# cameraTri-v1_1.net
KiCad netlist of a schematic drawn in Altium Designer
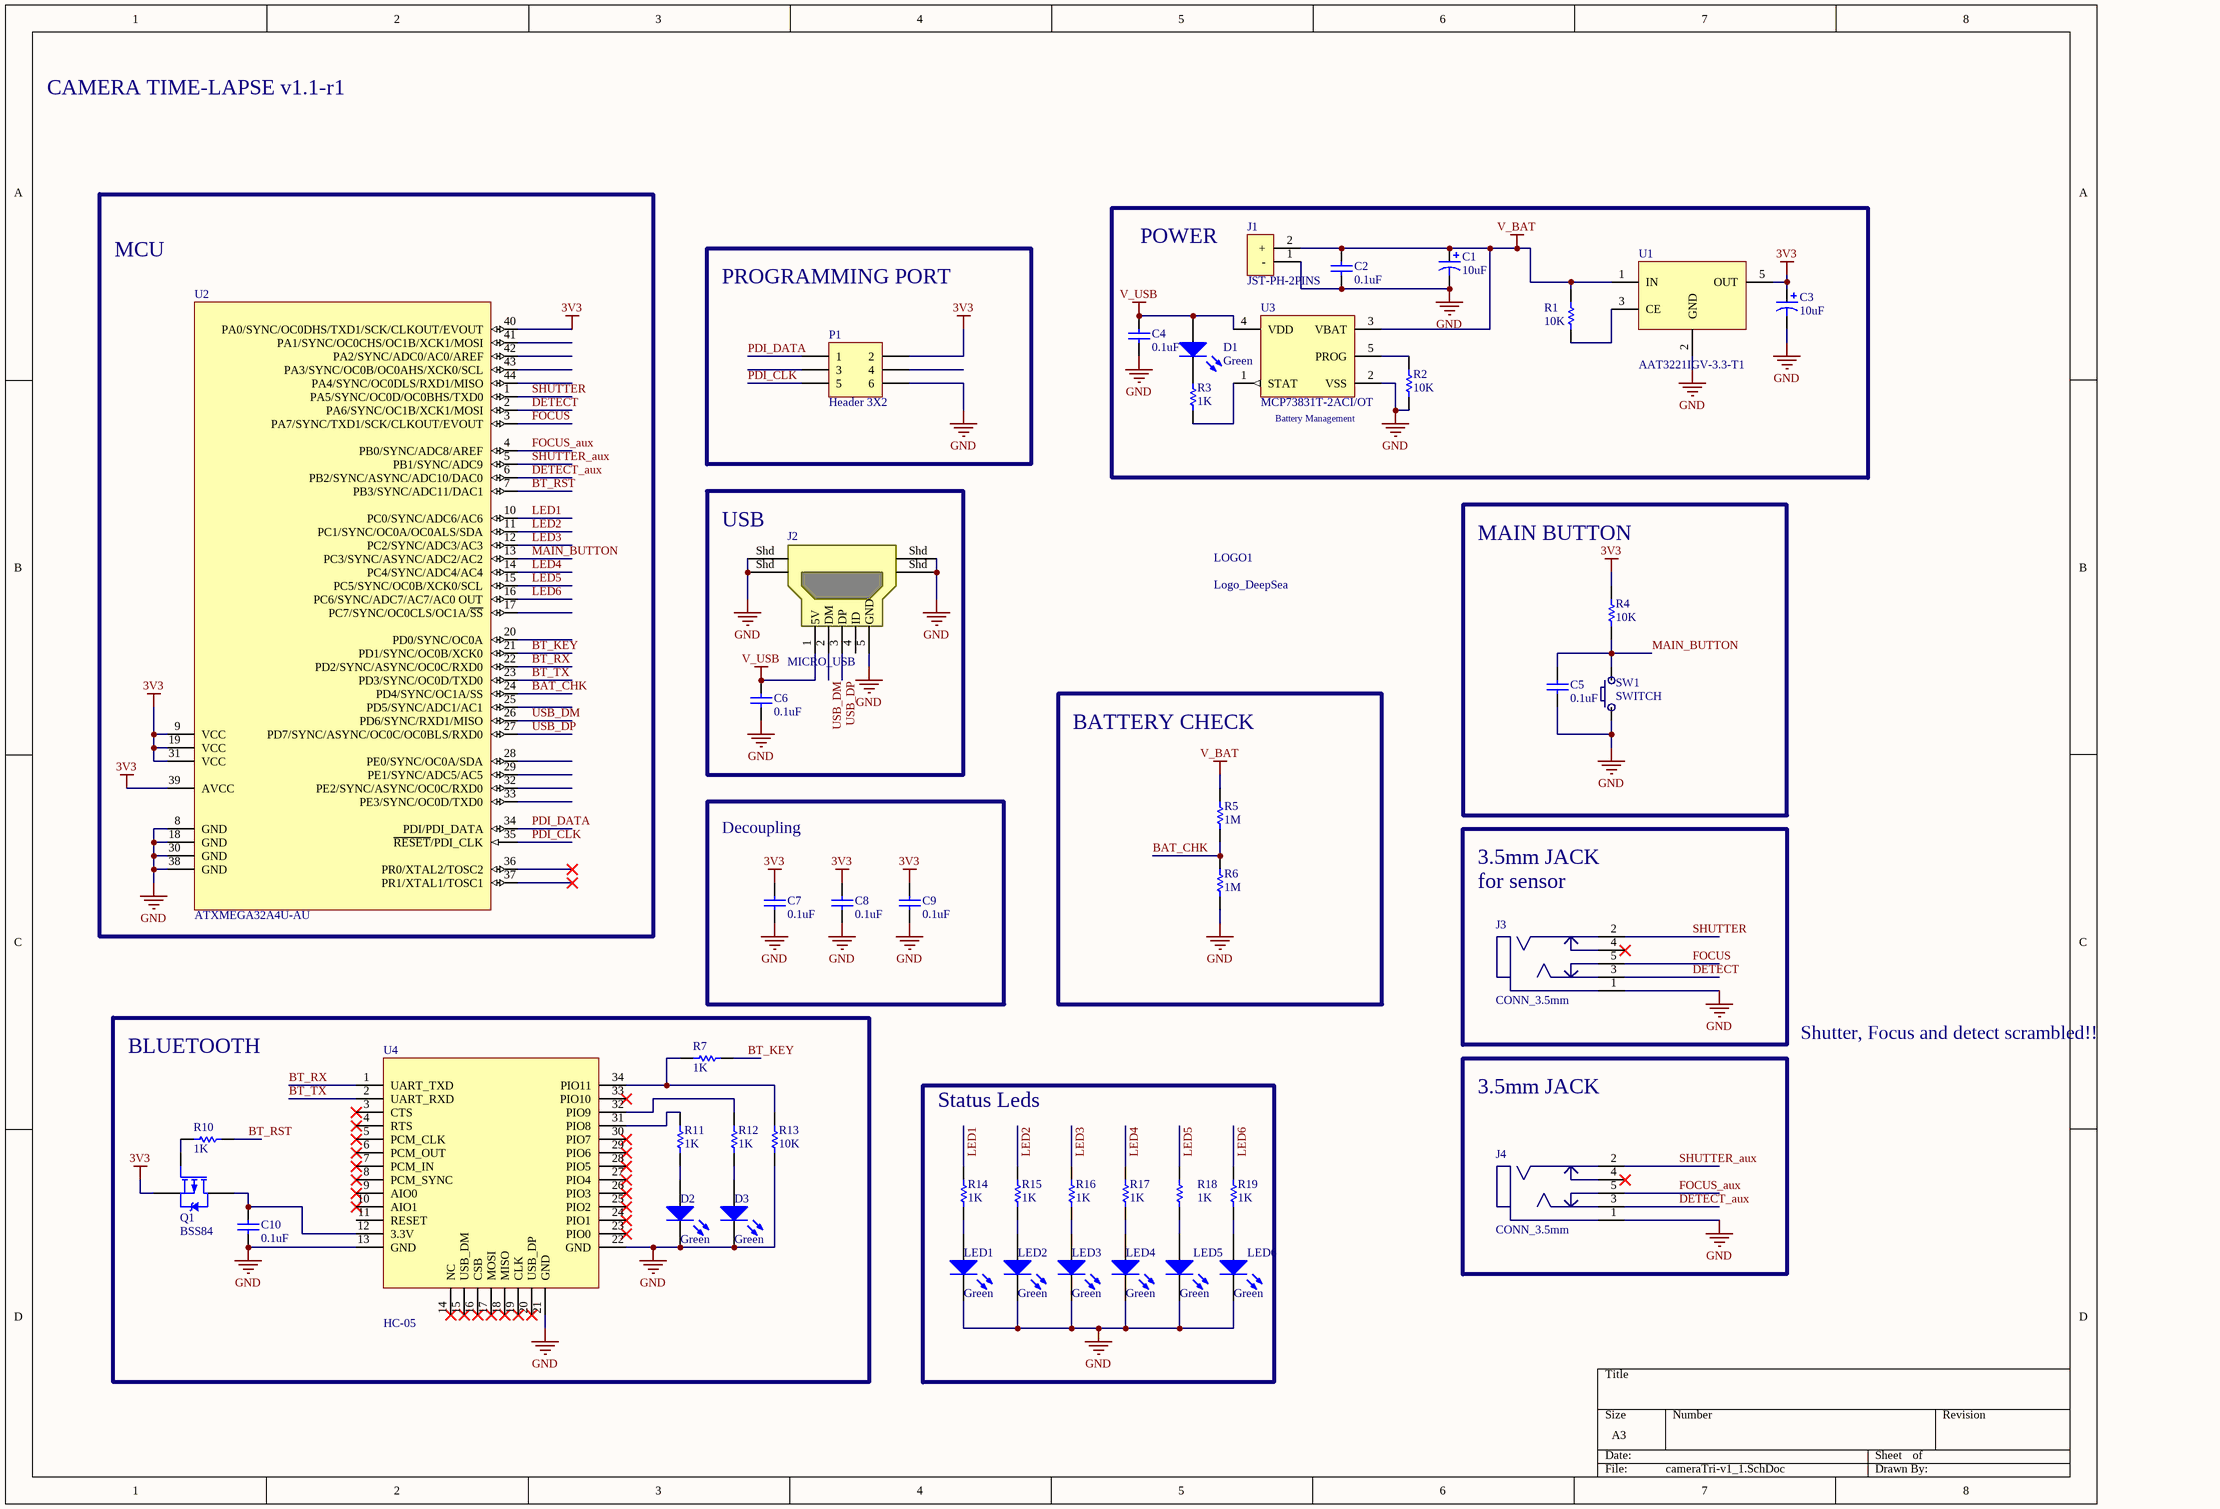
[diagram p0: cameraTri-v1_1.SchDoc]

(export (version "E")
  (design (tool "Eeschema 10.0.6"))
  (components
    (comp (ref "C1") (value "10uF") (footprint "C_TANT_A_3216_N") (libsource (lib "General") (part "CP_SMD")))
    (comp (ref "C2") (value "0.1uF") (footprint "C0603_N") (libsource (lib "General") (part "C_SMD")))
    (comp (ref "C3") (value "10uF") (footprint "C_TANT_A_3216_N") (libsource (lib "General") (part "CP_SMD")))
    (comp (ref "C4") (value "0.1uF") (footprint "C0603_N") (libsource (lib "General") (part "C_SMD")))
    (comp (ref "C5") (value "0.1uF") (footprint "C0603_N") (libsource (lib "General") (part "C_SMD")))
    (comp (ref "C6") (value "0.1uF") (footprint "C0603_N") (libsource (lib "General") (part "C_SMD")))
    (comp (ref "C7") (value "0.1uF") (footprint "C0603_N") (libsource (lib "General") (part "C_SMD")))
    (comp (ref "C8") (value "0.1uF") (footprint "C0603_N") (libsource (lib "General") (part "C_SMD")))
    (comp (ref "C9") (value "0.1uF") (footprint "C0603_N") (libsource (lib "General") (part "C_SMD")))
    (comp (ref "C10") (value "0.1uF") (footprint "C0603_N") (libsource (lib "General") (part "C_SMD")))
    (comp (ref "D1")
      (value "Green")
      (footprint "R0603_N")
      (fields (field (name "COLOR") "Green"))
      (libsource (lib "discrete") (part "LED_SMD"))
    )
    (comp (ref "D2")
      (value "Green")
      (footprint "R0603_N")
      (fields (field (name "COLOR") "Green"))
      (libsource (lib "discrete") (part "LED_SMD"))
    )
    (comp (ref "D3")
      (value "Green")
      (footprint "R0603_N")
      (fields (field (name "COLOR") "Green"))
      (libsource (lib "discrete") (part "LED_SMD"))
    )
    (comp (ref "J1")
      (value "JST-PH-2PINS")
      (footprint "JST-PH-2")
      (description "CONN HEADER PH SIDE 2POS 2MM SMD")
      (fields
        (field (name "MANUFACTURER") "JST Sales America Inc")
        (field (name "MANUFACTURER PART NUMBER") "S2B-PH-SM4-TB(LF)(SN)")
      )
      (libsource (lib "General") (part "JST-PH-2PINS"))
    )
    (comp (ref "J2")
      (value "MICRO_USB")
      (footprint "USB_MICRO_SMD")
      (description "CONN USB MICRO B RECPT SMT R/A")
      (fields (field (name "MANUFACTURER") "FCI") (field (name "MANUFACTURER PART NUMBER") "10118194-0001LF"))
      (libsource (lib "General") (part "MICRO_USB"))
    )
    (comp (ref "J3")
      (value "CONN_3.5mm")
      (footprint "JACK_3.5MM")
      (description "CONN JACK STEREO 3.5MM SMD")
      (fields
        (field (name "MANUFACTURER") "Switchcraft Inc.")
        (field (name "MANUFACTURER PART NUMBER") "35RASMT4BHNTRX")
      )
      (libsource (lib "General") (part "CONN_3.5mm"))
    )
    (comp (ref "J4")
      (value "CONN_3.5mm")
      (footprint "JACK_3.5MM")
      (description "CONN JACK STEREO 3.5MM SMD")
      (fields
        (field (name "MANUFACTURER") "Switchcraft Inc.")
        (field (name "MANUFACTURER PART NUMBER") "35RASMT4BHNTRX")
      )
      (libsource (lib "General") (part "CONN_3.5mm"))
    )
    (comp (ref "LED1")
      (value "Green")
      (footprint "R0603_N")
      (fields (field (name "COLOR") "Green"))
      (libsource (lib "discrete") (part "LED_SMD"))
    )
    (comp (ref "LED2")
      (value "Green")
      (footprint "R0603_N")
      (fields (field (name "COLOR") "Green"))
      (libsource (lib "discrete") (part "LED_SMD"))
    )
    (comp (ref "LED3")
      (value "Green")
      (footprint "R0603_N")
      (fields (field (name "COLOR") "Green"))
      (libsource (lib "discrete") (part "LED_SMD"))
    )
    (comp (ref "LED4")
      (value "Green")
      (footprint "R0603_N")
      (fields (field (name "COLOR") "Green"))
      (libsource (lib "discrete") (part "LED_SMD"))
    )
    (comp (ref "LED5")
      (value "Green")
      (footprint "R0603_N")
      (fields (field (name "COLOR") "Green"))
      (libsource (lib "discrete") (part "LED_SMD"))
    )
    (comp (ref "LED6")
      (value "Green")
      (footprint "R0603_N")
      (fields (field (name "COLOR") "Green"))
      (libsource (lib "discrete") (part "LED_SMD"))
    )
    (comp (ref "LOGO1")
      (value "Logo_DeepSea")
      (footprint "DeepSea_logo1")
      (libsource (lib "General") (part "Logo_DeepSea"))
    )
    (comp (ref "P1")
      (value "Header 3X2")
      (footprint "HDR2X3")
      (description "Header, 3-Pin, Dual row")
      (fields (field (name "PUBLISHER") "Altium Limited"))
      (libsource (lib "Miscellaneous Connectors") (part "Header 3X2"))
    )
    (comp (ref "Q1")
      (value "BSS84")
      (footprint "SOT-23_N")
      (description "MOSFET P-CH 50V 130MA SOT-23")
      (fields (field (name "MANUFACTURER") "Fairchild Semiconductor"))
      (libsource (lib "General") (part "BSS84"))
    )
    (comp (ref "R1") (value "10K") (footprint "R0603_N") (libsource (lib "discrete") (part "R_SMD")))
    (comp (ref "R2") (value "10K") (footprint "R0603_N") (libsource (lib "discrete") (part "R_SMD")))
    (comp (ref "R3") (value "1K") (footprint "R0603_N") (libsource (lib "discrete") (part "R_SMD")))
    (comp (ref "R4") (value "10K") (footprint "R0603_N") (libsource (lib "discrete") (part "R_SMD")))
    (comp (ref "R5") (value "1M") (footprint "R0603_N") (libsource (lib "discrete") (part "R_SMD")))
    (comp (ref "R6") (value "1M") (footprint "R0603_N") (libsource (lib "discrete") (part "R_SMD")))
    (comp (ref "R7") (value "1K") (footprint "R0603_N") (libsource (lib "discrete") (part "R_SMD")))
    (comp (ref "R10") (value "1K") (footprint "R0603_N") (libsource (lib "discrete") (part "R_SMD")))
    (comp (ref "R11") (value "1K") (footprint "R0603_N") (libsource (lib "discrete") (part "R_SMD")))
    (comp (ref "R12") (value "1K") (footprint "R0603_N") (libsource (lib "discrete") (part "R_SMD")))
    (comp (ref "R13") (value "10K") (footprint "R0603_N") (libsource (lib "discrete") (part "R_SMD")))
    (comp (ref "R14") (value "1K") (footprint "R0603_N") (libsource (lib "discrete") (part "R_SMD")))
    (comp (ref "R15") (value "1K") (footprint "R0603_N") (libsource (lib "discrete") (part "R_SMD")))
    (comp (ref "R16") (value "1K") (footprint "R0603_N") (libsource (lib "discrete") (part "R_SMD")))
    (comp (ref "R17") (value "1K") (footprint "R0603_N") (libsource (lib "discrete") (part "R_SMD")))
    (comp (ref "R18") (value "1K") (footprint "R0603_N") (libsource (lib "discrete") (part "R_SMD")))
    (comp (ref "R19") (value "1K") (footprint "R0603_N") (libsource (lib "discrete") (part "R_SMD")))
    (comp (ref "SW1")
      (value "SWITCH")
      (footprint "swich_foot")
      (description "SWITCH TACTILE SPST-NO 0.05A 12V")
      (fields
        (field (name "MANUFACTURER") "TE Connectivity")
        (field (name "MANUFACTURER PART NUMBER") "FSM4JSMATR")
      )
      (libsource (lib "General") (part "SWITCH"))
    )
    (comp (ref "U1")
      (value "AAT3221IGV-3.3-T1")
      (footprint "SOT-23-OT5_N")
      (description "IC REG LDO 3.3V 0.15A SOT23-5")
      (fields (field (name "MANUFACTURER") "Skyworks Solutions Inc"))
      (libsource (lib "General") (part "AAT3221IGV-3.3-T1"))
    )
    (comp (ref "U2")
      (value "ATXMEGA32A4U-AU")
      (footprint "44A_N")
      (description "IC MCU 8BIT 32KB FLASH 44TQFP")
      (fields (field (name "MANUFACTURER") "Atmel"))
      (libsource (lib "General") (part "ATXMEGA32A4U-AU"))
    )
    (comp (ref "U3")
      (value "MCP73831T-2ACI/OT")
      (footprint "SOT-23-OT5_N")
      (description "IC CONTROLLR LI-ION 4.2V SOT23-5")
      (fields (field (name "MANUFACTURER") "Microchip Technology"))
      (libsource (lib "General") (part "MCP73831T-2ACI/OT"))
    )
    (comp (ref "U4")
      (value "HC-05")
      (footprint "HC-05")
      (description "Bluetooth RS232 module")
      (libsource (lib "General") (part "HC-05"))
    )
  )
  (nets
    (net (code "1") (name "/BAT_CHK") (class "Default")
      (node (ref "R5") (pin "2") (pinfunction "2_2") (pintype "passive"))
      (node (ref "R6") (pin "1") (pinfunction "1_1") (pintype "passive"))
      (node (ref "U2") (pin "24") (pinfunction "PD4/SYNC/OC1A/SS_24") (pintype "bidirectional"))
    )
    (net (code "2") (name "/BT_KEY") (class "Default")
      (node (ref "R7") (pin "1") (pinfunction "1_1") (pintype "passive"))
      (node (ref "U2") (pin "21") (pinfunction "PD1/SYNC/OC0B/XCK0_21") (pintype "bidirectional"))
    )
    (net (code "3") (name "/BT_RST") (class "Default")
      (node (ref "R10") (pin "2") (pinfunction "2_2") (pintype "passive"))
      (node (ref "U2") (pin "7") (pinfunction "PB3/SYNC/ADC11/DAC1_7") (pintype "bidirectional"))
    )
    (net (code "4") (name "/BT_RX") (class "Default")
      (node (ref "U2") (pin "22") (pinfunction "PD2/SYNC/ASYNC/OC0C/RXD0_22") (pintype "bidirectional"))
      (node (ref "U4") (pin "1") (pinfunction "UART_TXD_1") (pintype "passive"))
    )
    (net (code "5") (name "/BT_TX") (class "Default")
      (node (ref "U2") (pin "23") (pinfunction "PD3/SYNC/OC0D/TXD0_23") (pintype "bidirectional"))
      (node (ref "U4") (pin "2") (pinfunction "UART_RXD_2") (pintype "passive"))
    )
    (net (code "6") (name "/DETECT") (class "Default")
      (node (ref "J3") (pin "3") (pintype "passive"))
      (node (ref "U2") (pin "2") (pinfunction "PA6/SYNC/OC1B/XCK1/MOSI_2") (pintype "bidirectional"))
    )
    (net (code "7") (name "/DETECT_aux") (class "Default")
      (node (ref "J4") (pin "3") (pintype "passive"))
      (node (ref "U2") (pin "6") (pinfunction "PB2/SYNC/ASYNC/ADC10/DAC0_6") (pintype "bidirectional"))
    )
    (net (code "8") (name "/FOCUS") (class "Default")
      (node (ref "J3") (pin "5") (pintype "passive"))
      (node (ref "U2") (pin "3") (pinfunction "PA7/SYNC/TXD1/SCK/CLKOUT/EVOUT_3") (pintype "bidirectional"))
    )
    (net (code "9") (name "/FOCUS_aux") (class "Default")
      (node (ref "J4") (pin "5") (pintype "passive"))
      (node (ref "U2") (pin "4") (pinfunction "PB0/SYNC/ADC8/AREF_4") (pintype "bidirectional"))
    )
    (net (code "10") (name "/LED1") (class "Default")
      (node (ref "R14") (pin "1") (pinfunction "1_1") (pintype "passive"))
      (node (ref "U2") (pin "10") (pinfunction "PC0/SYNC/ADC6/AC6_10") (pintype "bidirectional"))
    )
    (net (code "11") (name "/LED2") (class "Default")
      (node (ref "R15") (pin "1") (pinfunction "1_1") (pintype "passive"))
      (node (ref "U2") (pin "11") (pinfunction "PC1/SYNC/OC0A/OC0ALS/SDA_11") (pintype "bidirectional"))
    )
    (net (code "12") (name "/LED3") (class "Default")
      (node (ref "R16") (pin "1") (pinfunction "1_1") (pintype "passive"))
      (node (ref "U2") (pin "12") (pinfunction "PC2/SYNC/ADC3/AC3_12") (pintype "bidirectional"))
    )
    (net (code "13") (name "/LED4") (class "Default")
      (node (ref "R17") (pin "1") (pinfunction "1_1") (pintype "passive"))
      (node (ref "U2") (pin "14") (pinfunction "PC4/SYNC/ADC4/AC4_14") (pintype "bidirectional"))
    )
    (net (code "14") (name "/LED5") (class "Default")
      (node (ref "R18") (pin "1") (pinfunction "1_1") (pintype "passive"))
      (node (ref "U2") (pin "15") (pinfunction "PC5/SYNC/OC0B/XCK0/SCL_15") (pintype "bidirectional"))
    )
    (net (code "15") (name "/LED6") (class "Default")
      (node (ref "R19") (pin "1") (pinfunction "1_1") (pintype "passive"))
      (node (ref "U2") (pin "16") (pinfunction "PC6/SYNC/ADC7/AC7/AC0_OUT_16") (pintype "bidirectional"))
    )
    (net (code "16") (name "/MAIN_BUTTON") (class "Default")
      (node (ref "C5") (pin "1") (pinfunction "1_1") (pintype "passive"))
      (node (ref "R4") (pin "1") (pinfunction "1_1") (pintype "passive"))
      (node (ref "SW1") (pin "2") (pinfunction "*_2") (pintype "passive"))
      (node (ref "U2") (pin "13") (pinfunction "PC3/SYNC/ASYNC/ADC2/AC2_13") (pintype "bidirectional"))
    )
    (net (code "17") (name "/PDI_CLK") (class "Default")
      (node (ref "P1") (pin "5") (pinfunction "5_5") (pintype "passive"))
      (node (ref "U2") (pin "35") (pinfunction "~{RESET}/PDI_CLK_35") (pintype "input"))
    )
    (net (code "18") (name "/PDI_DATA") (class "Default")
      (node (ref "P1") (pin "1") (pinfunction "1_1") (pintype "passive"))
      (node (ref "U2") (pin "34") (pinfunction "PDI/PDI_DATA_34") (pintype "bidirectional"))
    )
    (net (code "19") (name "/SHUTTER") (class "Default")
      (node (ref "J3") (pin "2") (pintype "passive"))
      (node (ref "U2") (pin "1") (pinfunction "PA5/SYNC/OC0D/OC0BHS/TXD0_1") (pintype "bidirectional"))
    )
    (net (code "20") (name "/SHUTTER_aux") (class "Default")
      (node (ref "J4") (pin "2") (pintype "passive"))
      (node (ref "U2") (pin "5") (pinfunction "PB1/SYNC/ADC9_5") (pintype "bidirectional"))
    )
    (net (code "21") (name "/USB_DM") (class "Default")
      (node (ref "J2") (pin "2") (pinfunction "DM_2") (pintype "passive"))
      (node (ref "U2") (pin "26") (pinfunction "PD6/SYNC/RXD1/MISO_26") (pintype "bidirectional"))
    )
    (net (code "22") (name "/USB_DP") (class "Default")
      (node (ref "J2") (pin "3") (pinfunction "DP_3") (pintype "passive"))
      (node (ref "U2") (pin "27") (pinfunction "PD7/SYNC/ASYNC/OC0C/OC0BLS/RXD0_27") (pintype "bidirectional"))
    )
    (net (code "23") (name "3V3") (class "Default")
      (node (ref "C3") (pin "1") (pinfunction "1_1") (pintype "passive"))
      (node (ref "C7") (pin "2") (pinfunction "2_2") (pintype "passive"))
      (node (ref "C8") (pin "2") (pinfunction "2_2") (pintype "passive"))
      (node (ref "C9") (pin "2") (pinfunction "2_2") (pintype "passive"))
      (node (ref "P1") (pin "2") (pinfunction "2_2") (pintype "passive"))
      (node (ref "Q1") (pin "3") (pinfunction "S_3") (pintype "passive"))
      (node (ref "R4") (pin "2") (pinfunction "2_2") (pintype "passive"))
      (node (ref "U1") (pin "5") (pinfunction "OUT_5") (pintype "passive"))
      (node (ref "U2") (pin "19") (pinfunction "VCC_19") (pintype "power_in"))
      (node (ref "U2") (pin "31") (pinfunction "VCC_31") (pintype "power_in"))
      (node (ref "U2") (pin "39") (pinfunction "AVCC_39") (pintype "power_in"))
      (node (ref "U2") (pin "40") (pinfunction "PA0/SYNC/OC0DHS/TXD1/SCK/CLKOUT/EVOUT_40") (pintype "bidirectional"))
      (node (ref "U2") (pin "9") (pinfunction "VCC_9") (pintype "power_in"))
    )
    (net (code "24") (name "GND") (class "Default")
      (node (ref "C1") (pin "2") (pinfunction "2_2") (pintype "passive"))
      (node (ref "C10") (pin "1") (pinfunction "1_1") (pintype "passive"))
      (node (ref "C2") (pin "1") (pinfunction "1_1") (pintype "passive"))
      (node (ref "C3") (pin "2") (pinfunction "2_2") (pintype "passive"))
      (node (ref "C4") (pin "1") (pinfunction "1_1") (pintype "passive"))
      (node (ref "C5") (pin "2") (pinfunction "2_2") (pintype "passive"))
      (node (ref "C6") (pin "1") (pinfunction "1_1") (pintype "passive"))
      (node (ref "C7") (pin "1") (pinfunction "1_1") (pintype "passive"))
      (node (ref "C8") (pin "1") (pinfunction "1_1") (pintype "passive"))
      (node (ref "C9") (pin "1") (pinfunction "1_1") (pintype "passive"))
      (node (ref "D2") (pin "2") (pinfunction "K_2") (pintype "passive"))
      (node (ref "D3") (pin "2") (pinfunction "K_2") (pintype "passive"))
      (node (ref "J1") (pin "1") (pinfunction "-_1") (pintype "passive"))
      (node (ref "J2") (pin "5") (pinfunction "GND_5") (pintype "power_in"))
      (node (ref "J2") (pin "Shd") (pinfunction "6_Shd") (pintype "passive"))
      (node (ref "J3") (pin "1") (pintype "passive"))
      (node (ref "J4") (pin "1") (pintype "passive"))
      (node (ref "LED1") (pin "2") (pinfunction "K_2") (pintype "passive"))
      (node (ref "LED2") (pin "2") (pinfunction "K_2") (pintype "passive"))
      (node (ref "LED3") (pin "2") (pinfunction "K_2") (pintype "passive"))
      (node (ref "LED4") (pin "2") (pinfunction "K_2") (pintype "passive"))
      (node (ref "LED5") (pin "2") (pinfunction "K_2") (pintype "passive"))
      (node (ref "LED6") (pin "2") (pinfunction "K_2") (pintype "passive"))
      (node (ref "P1") (pin "6") (pinfunction "6_6") (pintype "passive"))
      (node (ref "R13") (pin "2") (pinfunction "2_2") (pintype "passive"))
      (node (ref "R2") (pin "1") (pinfunction "1_1") (pintype "passive"))
      (node (ref "R6") (pin "2") (pinfunction "2_2") (pintype "passive"))
      (node (ref "SW1") (pin "1") (pinfunction "*_1") (pintype "passive"))
      (node (ref "U1") (pin "2") (pinfunction "GND_2") (pintype "passive"))
      (node (ref "U2") (pin "18") (pinfunction "GND_18") (pintype "power_in"))
      (node (ref "U2") (pin "30") (pinfunction "GND_30") (pintype "power_in"))
      (node (ref "U2") (pin "38") (pinfunction "GND_38") (pintype "power_in"))
      (node (ref "U2") (pin "8") (pinfunction "GND_8") (pintype "power_in"))
      (node (ref "U3") (pin "2") (pinfunction "VSS_2") (pintype "power_in"))
      (node (ref "U4") (pin "13") (pinfunction "GND_13") (pintype "passive"))
      (node (ref "U4") (pin "21") (pinfunction "GND_21") (pintype "passive"))
      (node (ref "U4") (pin "22") (pinfunction "GND_22") (pintype "passive"))
    )
    (net (code "25") (name "Net-(D1-K)") (class "Default")
      (node (ref "D1") (pin "2") (pinfunction "K_2") (pintype "passive"))
      (node (ref "R3") (pin "1") (pinfunction "1_1") (pintype "passive"))
    )
    (net (code "26") (name "Net-(D2-A)") (class "Default")
      (node (ref "D2") (pin "1") (pinfunction "A_1") (pintype "passive"))
      (node (ref "R11") (pin "2") (pinfunction "2_2") (pintype "passive"))
    )
    (net (code "27") (name "Net-(D3-A)") (class "Default")
      (node (ref "D3") (pin "1") (pinfunction "A_1") (pintype "passive"))
      (node (ref "R12") (pin "2") (pinfunction "2_2") (pintype "passive"))
    )
    (net (code "28") (name "Net-(LED1-A)") (class "Default")
      (node (ref "LED1") (pin "1") (pinfunction "A_1") (pintype "passive"))
      (node (ref "R14") (pin "2") (pinfunction "2_2") (pintype "passive"))
    )
    (net (code "29") (name "Net-(LED2-A)") (class "Default")
      (node (ref "LED2") (pin "1") (pinfunction "A_1") (pintype "passive"))
      (node (ref "R15") (pin "2") (pinfunction "2_2") (pintype "passive"))
    )
    (net (code "30") (name "Net-(LED3-A)") (class "Default")
      (node (ref "LED3") (pin "1") (pinfunction "A_1") (pintype "passive"))
      (node (ref "R16") (pin "2") (pinfunction "2_2") (pintype "passive"))
    )
    (net (code "31") (name "Net-(LED4-A)") (class "Default")
      (node (ref "LED4") (pin "1") (pinfunction "A_1") (pintype "passive"))
      (node (ref "R17") (pin "2") (pinfunction "2_2") (pintype "passive"))
    )
    (net (code "32") (name "Net-(LED5-A)") (class "Default")
      (node (ref "LED5") (pin "1") (pinfunction "A_1") (pintype "passive"))
      (node (ref "R18") (pin "2") (pinfunction "2_2") (pintype "passive"))
    )
    (net (code "33") (name "Net-(LED6-A)") (class "Default")
      (node (ref "LED6") (pin "1") (pinfunction "A_1") (pintype "passive"))
      (node (ref "R19") (pin "2") (pinfunction "2_2") (pintype "passive"))
    )
    (net (code "34") (name "Net-(Q1-D)") (class "Default")
      (node (ref "C10") (pin "2") (pinfunction "2_2") (pintype "passive"))
      (node (ref "Q1") (pin "2") (pinfunction "D_2") (pintype "passive"))
      (node (ref "U4") (pin "12") (pinfunction "3.3V_12") (pintype "passive"))
    )
    (net (code "35") (name "Net-(Q1-G)") (class "Default")
      (node (ref "Q1") (pin "1") (pinfunction "G_1") (pintype "passive"))
      (node (ref "R10") (pin "1") (pinfunction "1_1") (pintype "passive"))
    )
    (net (code "36") (name "Net-(U1-CE)") (class "Default")
      (node (ref "R1") (pin "1") (pinfunction "1_1") (pintype "passive"))
      (node (ref "U1") (pin "3") (pinfunction "CE_3") (pintype "passive"))
    )
    (net (code "37") (name "Net-(U3-PROG)") (class "Default")
      (node (ref "R2") (pin "2") (pinfunction "2_2") (pintype "passive"))
      (node (ref "U3") (pin "5") (pinfunction "PROG_5") (pintype "passive"))
    )
    (net (code "38") (name "Net-(U3-STAT)") (class "Default")
      (node (ref "R3") (pin "2") (pinfunction "2_2") (pintype "passive"))
      (node (ref "U3") (pin "1") (pinfunction "STAT_1") (pintype "output"))
    )
    (net (code "39") (name "Net-(U4-PIO8)") (class "Default")
      (node (ref "R11") (pin "1") (pinfunction "1_1") (pintype "passive"))
      (node (ref "U4") (pin "31") (pinfunction "PIO8_31") (pintype "passive"))
    )
    (net (code "40") (name "Net-(U4-PIO9)") (class "Default")
      (node (ref "R12") (pin "1") (pinfunction "1_1") (pintype "passive"))
      (node (ref "U4") (pin "32") (pinfunction "PIO9_32") (pintype "passive"))
    )
    (net (code "41") (name "Net-(U4-PIO11)") (class "Default")
      (node (ref "R13") (pin "1") (pinfunction "1_1") (pintype "passive"))
      (node (ref "R7") (pin "2") (pinfunction "2_2") (pintype "passive"))
      (node (ref "U4") (pin "34") (pinfunction "PIO11_34") (pintype "passive"))
    )
    (net (code "42") (name "V_BAT") (class "Default")
      (node (ref "C1") (pin "1") (pinfunction "1_1") (pintype "passive"))
      (node (ref "C2") (pin "2") (pinfunction "2_2") (pintype "passive"))
      (node (ref "J1") (pin "2") (pinfunction "+_2") (pintype "passive"))
      (node (ref "R1") (pin "2") (pinfunction "2_2") (pintype "passive"))
      (node (ref "R5") (pin "1") (pinfunction "1_1") (pintype "passive"))
      (node (ref "U1") (pin "1") (pinfunction "IN_1") (pintype "passive"))
      (node (ref "U3") (pin "3") (pinfunction "VBAT_3") (pintype "power_in"))
    )
    (net (code "43") (name "V_USB") (class "Default")
      (node (ref "C4") (pin "2") (pinfunction "2_2") (pintype "passive"))
      (node (ref "C6") (pin "2") (pinfunction "2_2") (pintype "passive"))
      (node (ref "D1") (pin "1") (pinfunction "A_1") (pintype "passive"))
      (node (ref "J2") (pin "1") (pinfunction "5V_1") (pintype "power_in"))
      (node (ref "U3") (pin "4") (pinfunction "VDD_4") (pintype "power_in"))
    )
    (net (code "44") (name "unconnected-(J2-ID-Pad4)") (class "Default")
      (node (ref "J2") (pin "4") (pinfunction "ID_4") (pintype "passive"))
    )
    (net (code "45") (name "unconnected-(J3-Pad4)") (class "Default")
      (node (ref "J3") (pin "4") (pintype "passive+no_connect"))
    )
    (net (code "46") (name "unconnected-(J4-Pad4)") (class "Default")
      (node (ref "J4") (pin "4") (pintype "passive+no_connect"))
    )
    (net (code "47") (name "unconnected-(P1-Pad3)") (class "Default")
      (node (ref "P1") (pin "3") (pinfunction "3_3") (pintype "passive"))
    )
    (net (code "48") (name "unconnected-(P1-Pad4)") (class "Default")
      (node (ref "P1") (pin "4") (pinfunction "4_4") (pintype "passive"))
    )
    (net (code "49") (name "unconnected-(U2-PA1{slash}SYNC{slash}OC0CHS{slash}OC1B{slash}XCK1{slash}MOSI-Pad41)") (class "Default")
      (node (ref "U2") (pin "41") (pinfunction "PA1/SYNC/OC0CHS/OC1B/XCK1/MOSI_41") (pintype "bidirectional"))
    )
    (net (code "50") (name "unconnected-(U2-PA2{slash}SYNC{slash}ADC0{slash}AC0{slash}AREF-Pad42)") (class "Default")
      (node (ref "U2") (pin "42") (pinfunction "PA2/SYNC/ADC0/AC0/AREF_42") (pintype "bidirectional"))
    )
    (net (code "51") (name "unconnected-(U2-PA3{slash}SYNC{slash}OC0B{slash}OC0AHS{slash}XCK0{slash}SCL-Pad43)") (class "Default")
      (node (ref "U2") (pin "43") (pinfunction "PA3/SYNC/OC0B/OC0AHS/XCK0/SCL_43") (pintype "bidirectional"))
    )
    (net (code "52") (name "unconnected-(U2-PA4{slash}SYNC{slash}OC0DLS{slash}RXD1{slash}MISO-Pad44)") (class "Default")
      (node (ref "U2") (pin "44") (pinfunction "PA4/SYNC/OC0DLS/RXD1/MISO_44") (pintype "bidirectional"))
    )
    (net (code "53") (name "unconnected-(U2-PC7{slash}SYNC{slash}OC0CLS{slash}OC1A{slash}~{SS}-Pad17)") (class "Default")
      (node (ref "U2") (pin "17") (pinfunction "PC7/SYNC/OC0CLS/OC1A/~{SS}_17") (pintype "bidirectional"))
    )
    (net (code "54") (name "unconnected-(U2-PD0{slash}SYNC{slash}OC0A-Pad20)") (class "Default")
      (node (ref "U2") (pin "20") (pinfunction "PD0/SYNC/OC0A_20") (pintype "bidirectional"))
    )
    (net (code "55") (name "unconnected-(U2-PD5{slash}SYNC{slash}ADC1{slash}AC1-Pad25)") (class "Default")
      (node (ref "U2") (pin "25") (pinfunction "PD5/SYNC/ADC1/AC1_25") (pintype "bidirectional"))
    )
    (net (code "56") (name "unconnected-(U2-PE0{slash}SYNC{slash}OC0A{slash}SDA-Pad28)") (class "Default")
      (node (ref "U2") (pin "28") (pinfunction "PE0/SYNC/OC0A/SDA_28") (pintype "bidirectional"))
    )
    (net (code "57") (name "unconnected-(U2-PE1{slash}SYNC{slash}ADC5{slash}AC5-Pad29)") (class "Default")
      (node (ref "U2") (pin "29") (pinfunction "PE1/SYNC/ADC5/AC5_29") (pintype "bidirectional"))
    )
    (net (code "58") (name "unconnected-(U2-PE2{slash}SYNC{slash}ASYNC{slash}OC0C{slash}RXD0-Pad32)") (class "Default")
      (node (ref "U2") (pin "32") (pinfunction "PE2/SYNC/ASYNC/OC0C/RXD0_32") (pintype "bidirectional"))
    )
    (net (code "59") (name "unconnected-(U2-PE3{slash}SYNC{slash}OC0D{slash}TXD0-Pad33)") (class "Default")
      (node (ref "U2") (pin "33") (pinfunction "PE3/SYNC/OC0D/TXD0_33") (pintype "bidirectional"))
    )
    (net (code "60") (name "unconnected-(U2-PR0{slash}XTAL2{slash}TOSC2-Pad36)") (class "Default")
      (node (ref "U2") (pin "36") (pinfunction "PR0/XTAL2/TOSC2_36") (pintype "bidirectional+no_connect"))
    )
    (net (code "61") (name "unconnected-(U2-PR1{slash}XTAL1{slash}TOSC1-Pad37)") (class "Default")
      (node (ref "U2") (pin "37") (pinfunction "PR1/XTAL1/TOSC1_37") (pintype "bidirectional+no_connect"))
    )
    (net (code "62") (name "unconnected-(U4-AIO0-Pad9)") (class "Default")
      (node (ref "U4") (pin "9") (pinfunction "AIO0_9") (pintype "passive+no_connect"))
    )
    (net (code "63") (name "unconnected-(U4-AIO1-Pad10)") (class "Default")
      (node (ref "U4") (pin "10") (pinfunction "AIO1_10") (pintype "passive+no_connect"))
    )
    (net (code "64") (name "unconnected-(U4-CLK-Pad19)") (class "Default")
      (node (ref "U4") (pin "19") (pinfunction "CLK_19") (pintype "passive+no_connect"))
    )
    (net (code "65") (name "unconnected-(U4-CSB-Pad16)") (class "Default")
      (node (ref "U4") (pin "16") (pinfunction "CSB_16") (pintype "passive+no_connect"))
    )
    (net (code "66") (name "unconnected-(U4-CTS-Pad3)") (class "Default")
      (node (ref "U4") (pin "3") (pinfunction "CTS_3") (pintype "passive+no_connect"))
    )
    (net (code "67") (name "unconnected-(U4-MISO-Pad18)") (class "Default")
      (node (ref "U4") (pin "18") (pinfunction "MISO_18") (pintype "passive+no_connect"))
    )
    (net (code "68") (name "unconnected-(U4-MOSI-Pad17)") (class "Default")
      (node (ref "U4") (pin "17") (pinfunction "MOSI_17") (pintype "passive+no_connect"))
    )
    (net (code "69") (name "unconnected-(U4-NC-Pad14)") (class "Default")
      (node (ref "U4") (pin "14") (pinfunction "NC_14") (pintype "passive+no_connect"))
    )
    (net (code "70") (name "unconnected-(U4-PCM_CLK-Pad5)") (class "Default")
      (node (ref "U4") (pin "5") (pinfunction "PCM_CLK_5") (pintype "passive+no_connect"))
    )
    (net (code "71") (name "unconnected-(U4-PCM_IN-Pad7)") (class "Default")
      (node (ref "U4") (pin "7") (pinfunction "PCM_IN_7") (pintype "passive+no_connect"))
    )
    (net (code "72") (name "unconnected-(U4-PCM_OUT-Pad6)") (class "Default")
      (node (ref "U4") (pin "6") (pinfunction "PCM_OUT_6") (pintype "passive+no_connect"))
    )
    (net (code "73") (name "unconnected-(U4-PCM_SYNC-Pad8)") (class "Default")
      (node (ref "U4") (pin "8") (pinfunction "PCM_SYNC_8") (pintype "passive+no_connect"))
    )
    (net (code "74") (name "unconnected-(U4-PIO0-Pad23)") (class "Default")
      (node (ref "U4") (pin "23") (pinfunction "PIO0_23") (pintype "passive+no_connect"))
    )
    (net (code "75") (name "unconnected-(U4-PIO1-Pad24)") (class "Default")
      (node (ref "U4") (pin "24") (pinfunction "PIO1_24") (pintype "passive+no_connect"))
    )
    (net (code "76") (name "unconnected-(U4-PIO2-Pad25)") (class "Default")
      (node (ref "U4") (pin "25") (pinfunction "PIO2_25") (pintype "passive+no_connect"))
    )
    (net (code "77") (name "unconnected-(U4-PIO3-Pad26)") (class "Default")
      (node (ref "U4") (pin "26") (pinfunction "PIO3_26") (pintype "passive+no_connect"))
    )
    (net (code "78") (name "unconnected-(U4-PIO4-Pad27)") (class "Default")
      (node (ref "U4") (pin "27") (pinfunction "PIO4_27") (pintype "passive+no_connect"))
    )
    (net (code "79") (name "unconnected-(U4-PIO5-Pad28)") (class "Default")
      (node (ref "U4") (pin "28") (pinfunction "PIO5_28") (pintype "passive+no_connect"))
    )
    (net (code "80") (name "unconnected-(U4-PIO6-Pad29)") (class "Default")
      (node (ref "U4") (pin "29") (pinfunction "PIO6_29") (pintype "passive+no_connect"))
    )
    (net (code "81") (name "unconnected-(U4-PIO7-Pad30)") (class "Default")
      (node (ref "U4") (pin "30") (pinfunction "PIO7_30") (pintype "passive+no_connect"))
    )
    (net (code "82") (name "unconnected-(U4-PIO10-Pad33)") (class "Default")
      (node (ref "U4") (pin "33") (pinfunction "PIO10_33") (pintype "passive+no_connect"))
    )
    (net (code "83") (name "unconnected-(U4-RESET-Pad11)") (class "Default")
      (node (ref "U4") (pin "11") (pinfunction "RESET_11") (pintype "passive"))
    )
    (net (code "84") (name "unconnected-(U4-RTS-Pad4)") (class "Default")
      (node (ref "U4") (pin "4") (pinfunction "RTS_4") (pintype "passive+no_connect"))
    )
    (net (code "85") (name "unconnected-(U4-USB_DM-Pad15)") (class "Default")
      (node (ref "U4") (pin "15") (pinfunction "USB_DM_15") (pintype "passive+no_connect"))
    )
    (net (code "86") (name "unconnected-(U4-USB_DP-Pad20)") (class "Default")
      (node (ref "U4") (pin "20") (pinfunction "USB_DP_20") (pintype "passive+no_connect"))
    )
  )
)
